# statim_board2.net
KiCad netlist of a schematic drawn in EAGLE
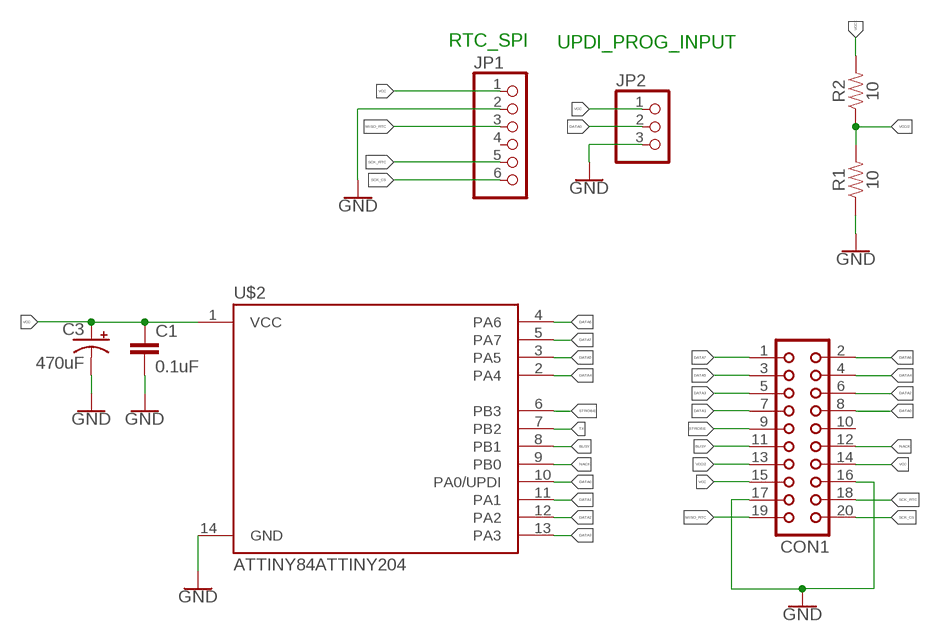
[diagram p0: schematic, sheet 1]

(export (version "E")
  (design (tool "Eeschema 10.0.6"))
  (components
    (comp (ref "C1")
      (value "0.1uF")
      (footprint "eagle-import:1206")
      (libsource (lib "eagle-import") (part "1.0UF-1206-50V-10%"))
    )
    (comp (ref "C3")
      (value "470uF")
      (footprint "eagle-import:PANASONIC_G")
      (libsource (lib "eagle-import") (part "560UF-PANASONIC_G-25V-20%"))
    )
    (comp (ref "CON1")
      (value "CON20")
      (footprint "eagle-import:CON20")
      (libsource (lib "eagle-import") (part "CON20"))
    )
    (comp (ref "JP1")
      (value "PINHD-1X6")
      (footprint "eagle-import:1X06")
      (libsource (lib "eagle-import") (part "PINHD-1X6"))
    )
    (comp (ref "JP2")
      (value "PINHD-1X3")
      (footprint "eagle-import:1X03")
      (libsource (lib "eagle-import") (part "PINHD-1X3"))
    )
    (comp (ref "R1")
      (value "10")
      (footprint "eagle-import:1206")
      (libsource (lib "eagle-import") (part "10OHM-1206-1/4W-1%"))
    )
    (comp (ref "R2")
      (value "10")
      (footprint "eagle-import:1206")
      (libsource (lib "eagle-import") (part "10OHM-1206-1/4W-1%"))
    )
    (comp (ref "U$2")
      (value "ATTINY84ATTINY204")
      (footprint "eagle-import:SO14")
      (libsource (lib "eagle-import") (part "ATTINY84ATTINY204"))
    )
  )
  (nets
    (net (code "1") (name "BUSY") (class "Default")
      (node (ref "CON1") (pin "11") (pinfunction "11_11") (pintype "passive"))
      (node (ref "U$2") (pin "8") (pinfunction "PB1_8") (pintype "bidirectional"))
    )
    (net (code "2") (name "DATA0") (class "Default")
      (node (ref "CON1") (pin "8") (pinfunction "8_8") (pintype "passive"))
      (node (ref "JP2") (pin "2") (pinfunction "2_2") (pintype "passive"))
      (node (ref "U$2") (pin "10") (pinfunction "PA0/UPDI_10") (pintype "bidirectional"))
    )
    (net (code "3") (name "DATA1") (class "Default")
      (node (ref "CON1") (pin "7") (pinfunction "7_7") (pintype "passive"))
      (node (ref "U$2") (pin "11") (pinfunction "PA1_11") (pintype "bidirectional"))
    )
    (net (code "4") (name "DATA2") (class "Default")
      (node (ref "CON1") (pin "6") (pinfunction "6_6") (pintype "passive"))
      (node (ref "U$2") (pin "12") (pinfunction "PA2_12") (pintype "bidirectional"))
    )
    (net (code "5") (name "DATA3") (class "Default")
      (node (ref "CON1") (pin "5") (pinfunction "5_5") (pintype "passive"))
      (node (ref "U$2") (pin "13") (pinfunction "PA3_13") (pintype "bidirectional"))
    )
    (net (code "6") (name "DATA4") (class "Default")
      (node (ref "CON1") (pin "4") (pinfunction "4_4") (pintype "passive"))
      (node (ref "U$2") (pin "2") (pinfunction "PA4_2") (pintype "bidirectional"))
    )
    (net (code "7") (name "DATA5") (class "Default")
      (node (ref "CON1") (pin "3") (pinfunction "3_3") (pintype "passive"))
      (node (ref "U$2") (pin "3") (pinfunction "PA5_3") (pintype "bidirectional"))
    )
    (net (code "8") (name "DATA6") (class "Default")
      (node (ref "CON1") (pin "2") (pinfunction "2_2") (pintype "passive"))
      (node (ref "U$2") (pin "4") (pinfunction "PA6_4") (pintype "bidirectional"))
    )
    (net (code "9") (name "DATA7") (class "Default")
      (node (ref "CON1") (pin "1") (pinfunction "1_1") (pintype "passive"))
      (node (ref "U$2") (pin "5") (pinfunction "PA7_5") (pintype "bidirectional"))
    )
    (net (code "10") (name "GND") (class "Default")
      (node (ref "C1") (pin "2") (pinfunction "2_2") (pintype "passive"))
      (node (ref "C3") (pin "-") (pinfunction "-_-") (pintype "passive"))
      (node (ref "CON1") (pin "16") (pinfunction "16_16") (pintype "passive"))
      (node (ref "CON1") (pin "17") (pinfunction "17_17") (pintype "passive"))
      (node (ref "JP1") (pin "2") (pinfunction "2_2") (pintype "passive"))
      (node (ref "JP2") (pin "3") (pinfunction "3_3") (pintype "passive"))
      (node (ref "R1") (pin "1") (pinfunction "1_1") (pintype "passive"))
      (node (ref "U$2") (pin "14") (pinfunction "GND_14") (pintype "bidirectional"))
    )
    (net (code "11") (name "MISO_RTC") (class "Default")
      (node (ref "CON1") (pin "19") (pinfunction "19_19") (pintype "passive"))
      (node (ref "JP1") (pin "3") (pinfunction "3_3") (pintype "passive"))
    )
    (net (code "12") (name "NACK") (class "Default")
      (node (ref "CON1") (pin "12") (pinfunction "12_12") (pintype "passive"))
      (node (ref "U$2") (pin "9") (pinfunction "PB0_9") (pintype "bidirectional"))
    )
    (net (code "13") (name "SCK_CS") (class "Default")
      (node (ref "CON1") (pin "20") (pinfunction "20_20") (pintype "passive"))
      (node (ref "JP1") (pin "6") (pinfunction "6_6") (pintype "passive"))
    )
    (net (code "14") (name "SCK_RTC") (class "Default")
      (node (ref "CON1") (pin "18") (pinfunction "18_18") (pintype "passive"))
      (node (ref "JP1") (pin "5") (pinfunction "5_5") (pintype "passive"))
    )
    (net (code "15") (name "STROBE") (class "Default")
      (node (ref "CON1") (pin "9") (pinfunction "9_9") (pintype "passive"))
      (node (ref "U$2") (pin "6") (pinfunction "PB3_6") (pintype "bidirectional"))
    )
    (net (code "16") (name "TX") (class "Default")
      (node (ref "U$2") (pin "7") (pinfunction "PB2_7") (pintype "bidirectional"))
    )
    (net (code "17") (name "VCC") (class "Default")
      (node (ref "C1") (pin "1") (pinfunction "1_1") (pintype "passive"))
      (node (ref "C3") (pin "+") (pinfunction "+_+") (pintype "passive"))
      (node (ref "CON1") (pin "14") (pinfunction "14_14") (pintype "passive"))
      (node (ref "CON1") (pin "15") (pinfunction "15_15") (pintype "passive"))
      (node (ref "JP1") (pin "1") (pinfunction "1_1") (pintype "passive"))
      (node (ref "JP2") (pin "1") (pinfunction "1_1") (pintype "passive"))
      (node (ref "R2") (pin "2") (pinfunction "2_2") (pintype "passive"))
      (node (ref "U$2") (pin "1") (pinfunction "VCC_1") (pintype "bidirectional"))
    )
    (net (code "18") (name "VCC{slash}2") (class "Default")
      (node (ref "CON1") (pin "13") (pinfunction "13_13") (pintype "passive"))
      (node (ref "R1") (pin "2") (pinfunction "2_2") (pintype "passive"))
      (node (ref "R2") (pin "1") (pinfunction "1_1") (pintype "passive"))
    )
    (net (code "19") (name "unconnected-(CON1-Pad10)") (class "Default")
      (node (ref "CON1") (pin "10") (pinfunction "10_10") (pintype "passive"))
    )
    (net (code "20") (name "unconnected-(JP1-Pad4)") (class "Default")
      (node (ref "JP1") (pin "4") (pinfunction "4_4") (pintype "passive"))
    )
  )
)
